# CON_REVD.net
KiCad netlist of a schematic drawn in Altium Designer
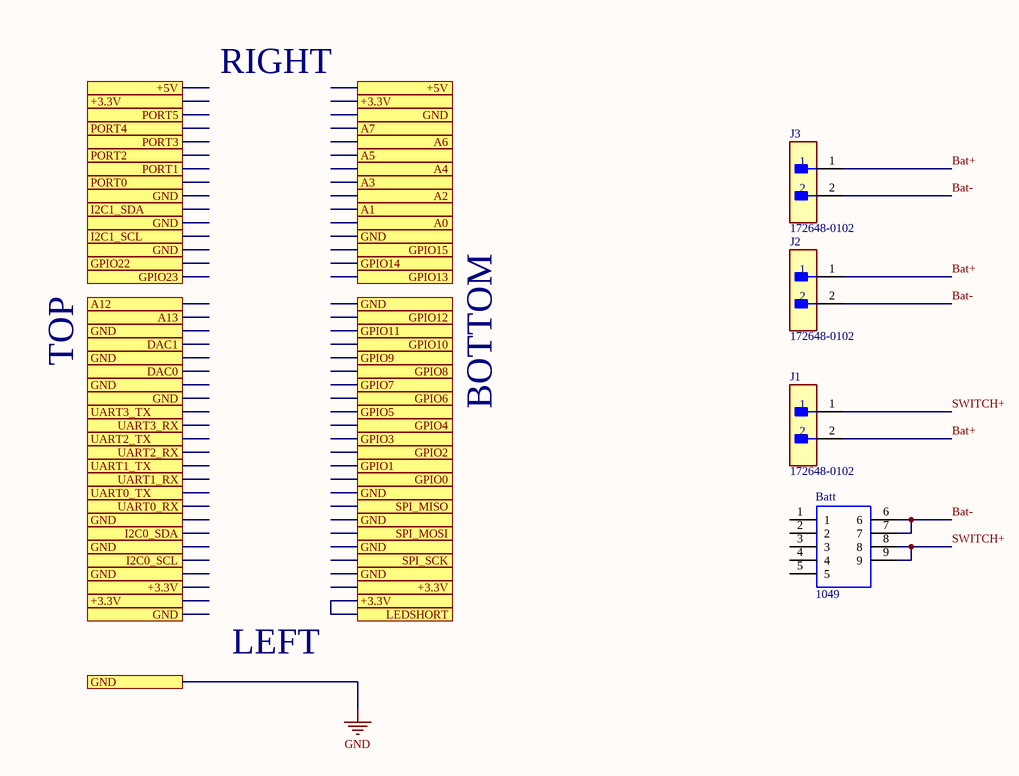
[diagram p0: CON_REVD.SchDoc]

(export (version "E")
  (design (tool "Eeschema 10.0.6"))
  (components
    (comp (ref "Batt")
      (value "1049")
      (footprint "1049:1049")
      (description "KEYSTONE - 1049 - BATTERY HOLDER, 18650, THROUGH HOLE")
      (fields (field (name "MOUSER PART NUMBER") "534-1049"))
      (libsource (lib "Connector_REVD") (part "1049"))
    )
    (comp (ref "J1")
      (value "172648-0102")
      (footprint "FP-172648-0102-MFG")
      (description "CONN HEADER R/A 2POS 4.2MM")
      (libsource (lib "Altium Content Vault") (part "88c1139f9d239099ffebecbe3f7647a"))
    )
    (comp (ref "J2")
      (value "172648-0102")
      (footprint "FP-172648-0102-MFG")
      (description "CONN HEADER R/A 2POS 4.2MM")
      (libsource (lib "Altium Content Vault") (part "88c1139f9d239099ffebecbe3f7647a"))
    )
    (comp (ref "J3")
      (value "172648-0102")
      (footprint "FP-172648-0102-MFG")
      (description "CONN HEADER R/A 2POS 4.2MM")
      (libsource (lib "Altium Content Vault") (part "88c1139f9d239099ffebecbe3f7647a"))
    )
  )
  (nets
    (net (code "13") (name "/Bat+") (class "Default")
      (node (ref "J1") (pin "2") (pinfunction "2_2") (pintype "passive"))
      (node (ref "J2") (pin "1") (pinfunction "1_1") (pintype "passive"))
      (node (ref "J3") (pin "1") (pinfunction "1_1") (pintype "passive"))
    )
    (net (code "14") (name "/Bat-") (class "Default")
      (node (ref "Batt") (pin "6") (pinfunction "6_6") (pintype "passive"))
      (node (ref "Batt") (pin "7") (pinfunction "7_7") (pintype "passive"))
      (node (ref "J2") (pin "2") (pinfunction "2_2") (pintype "passive"))
      (node (ref "J3") (pin "2") (pinfunction "2_2") (pintype "passive"))
    )
    (net (code "48") (name "/SWITCH+") (class "Default")
      (node (ref "Batt") (pin "8") (pinfunction "8_8") (pintype "passive"))
      (node (ref "Batt") (pin "9") (pinfunction "9_9") (pintype "passive"))
      (node (ref "J1") (pin "1") (pinfunction "1_1") (pintype "passive"))
    )
    (net (code "58") (name "unconnected-(Batt-Pad1)") (class "Default")
      (node (ref "Batt") (pin "1") (pinfunction "1_1") (pintype "passive"))
    )
    (net (code "59") (name "unconnected-(Batt-Pad2)") (class "Default")
      (node (ref "Batt") (pin "2") (pinfunction "2_2") (pintype "passive"))
    )
    (net (code "60") (name "unconnected-(Batt-Pad3)") (class "Default")
      (node (ref "Batt") (pin "3") (pinfunction "3_3") (pintype "passive"))
    )
    (net (code "61") (name "unconnected-(Batt-Pad4)") (class "Default")
      (node (ref "Batt") (pin "4") (pinfunction "4_4") (pintype "passive"))
    )
    (net (code "62") (name "unconnected-(Batt-Pad5)") (class "Default")
      (node (ref "Batt") (pin "5") (pinfunction "5_5") (pintype "passive"))
    )
  )
)
